# MARINEFORD.net
KiCad netlist of a schematic drawn in EAGLE
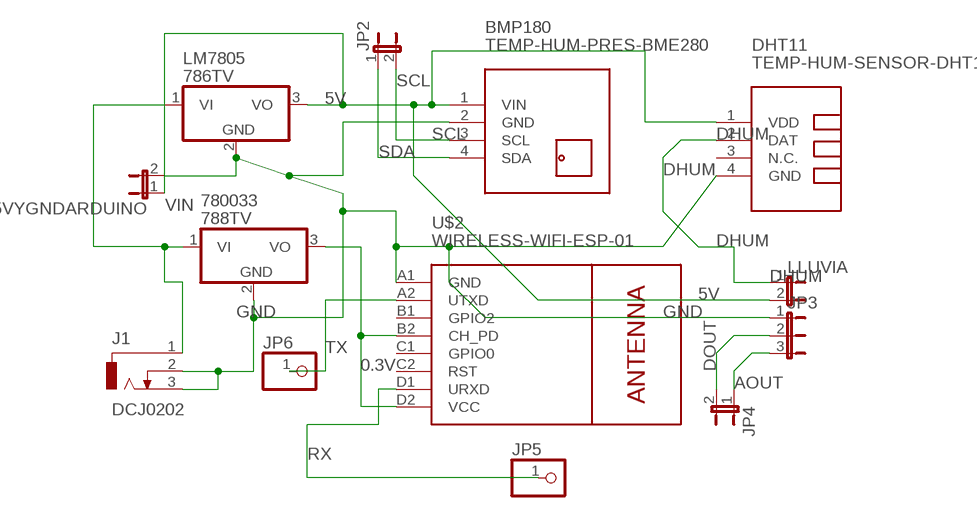
[diagram p0: schematic, sheet 1]

(export (version "E")
  (design (tool "Eeschema 10.0.6"))
  (components
    (comp (ref "5VYGNDARDUINO")
      (value "JP1E")
      (footprint "eagle-import:JP1")
      (libsource (lib "eagle-import") (part "JP1E"))
    )
    (comp (ref "780033")
      (value "788TV")
      (footprint "eagle-import:TO220V")
      (libsource (lib "eagle-import") (part "78TV8"))
    )
    (comp (ref "BMP180")
      (value "TEMP-HUM-PRES-BME280")
      (footprint "eagle-import:TEMP-HUM-PRES-BME280")
      (libsource (lib "eagle-import") (part "TEMP-HUM-PRES-BME280"))
    )
    (comp (ref "DHT11")
      (value "TEMP-HUM-SENSOR-DHT11")
      (footprint "eagle-import:TEMP-HUM-SENSOR-DHT11")
      (libsource (lib "eagle-import") (part "TEMP-HUM-SENSOR-DHT11"))
    )
    (comp (ref "J1")
      (value "DCJ0202")
      (footprint "eagle-import:DCJ0202")
      (libsource (lib "eagle-import") (part "DCJ0202"))
    )
    (comp (ref "JP2")
      (value "JP1E")
      (footprint "eagle-import:JP1")
      (libsource (lib "eagle-import") (part "JP1E"))
    )
    (comp (ref "JP3")
      (value "JP2E")
      (footprint "eagle-import:JP2")
      (libsource (lib "eagle-import") (part "JP2E"))
    )
    (comp (ref "JP4")
      (value "JP1E")
      (footprint "eagle-import:JP1")
      (libsource (lib "eagle-import") (part "JP1E"))
    )
    (comp (ref "JP5")
      (value "PINHD-1X1")
      (footprint "eagle-import:1X01")
      (libsource (lib "eagle-import") (part "PINHD-1X1"))
    )
    (comp (ref "JP6")
      (value "PINHD-1X1")
      (footprint "eagle-import:1X01")
      (libsource (lib "eagle-import") (part "PINHD-1X1"))
    )
    (comp (ref "LLUVIA")
      (value "JP1E")
      (footprint "eagle-import:JP1")
      (libsource (lib "eagle-import") (part "JP1E"))
    )
    (comp (ref "LM7805")
      (value "786TV")
      (footprint "eagle-import:TO220V")
      (libsource (lib "eagle-import") (part "78TV6"))
    )
    (comp (ref "U$2")
      (value "WIRELESS-WIFI-ESP-01")
      (footprint "eagle-import:WIRELESS-WIFI-ESP-01")
      (libsource (lib "eagle-import") (part "WIRELESS-WIFI-ESP-01"))
    )
  )
  (nets
    (net (code "1") (name "/0.3V") (class "Default")
      (node (ref "780033") (pin "3") (pinfunction "VO_3") (pintype "passive"))
      (node (ref "U$2") (pin "B2") (pinfunction "CH_PD_B2") (pintype "bidirectional"))
      (node (ref "U$2") (pin "D2") (pinfunction "VCC_D2") (pintype "power_in"))
    )
    (net (code "2") (name "/5V") (class "Default")
      (node (ref "5VYGNDARDUINO") (pin "1") (pinfunction "1_1") (pintype "passive"))
      (node (ref "BMP180") (pin "1") (pinfunction "VIN_1") (pintype "power_in"))
      (node (ref "DHT11") (pin "1") (pinfunction "VDD_1") (pintype "power_in"))
      (node (ref "LLUVIA") (pin "2") (pinfunction "2_2") (pintype "passive"))
      (node (ref "LM7805") (pin "3") (pinfunction "VO_3") (pintype "passive"))
    )
    (net (code "3") (name "/AOUT") (class "Default")
      (node (ref "JP3") (pin "3") (pinfunction "3_3") (pintype "passive"))
      (node (ref "JP4") (pin "1") (pinfunction "1_1") (pintype "passive"))
    )
    (net (code "4") (name "/DHUM") (class "Default")
      (node (ref "DHT11") (pin "2") (pinfunction "DAT_2") (pintype "bidirectional"))
      (node (ref "LLUVIA") (pin "1") (pinfunction "1_1") (pintype "passive"))
    )
    (net (code "5") (name "/DOUT") (class "Default")
      (node (ref "JP3") (pin "2") (pinfunction "2_2") (pintype "passive"))
      (node (ref "JP4") (pin "2") (pinfunction "2_2") (pintype "passive"))
    )
    (net (code "6") (name "/GND") (class "Default")
      (node (ref "5VYGNDARDUINO") (pin "2") (pinfunction "2_2") (pintype "passive"))
      (node (ref "780033") (pin "2") (pinfunction "GND_2") (pintype "passive"))
      (node (ref "BMP180") (pin "2") (pinfunction "GND_2") (pintype "power_in"))
      (node (ref "DHT11") (pin "4") (pinfunction "GND_4") (pintype "power_in"))
      (node (ref "J1") (pin "2") (pinfunction "2_2") (pintype "passive"))
      (node (ref "J1") (pin "3") (pinfunction "3_3") (pintype "passive"))
      (node (ref "JP3") (pin "1") (pinfunction "1_1") (pintype "passive"))
      (node (ref "LM7805") (pin "2") (pinfunction "GND_2") (pintype "passive"))
      (node (ref "U$2") (pin "A1") (pinfunction "GND_A1") (pintype "power_in"))
    )
    (net (code "7") (name "/RX") (class "Default")
      (node (ref "JP5") (pin "1") (pinfunction "1_1") (pintype "passive"))
      (node (ref "U$2") (pin "D1") (pinfunction "URXD_D1") (pintype "bidirectional"))
    )
    (net (code "8") (name "/SCL") (class "Default")
      (node (ref "BMP180") (pin "3") (pinfunction "SCL_3") (pintype "bidirectional"))
      (node (ref "JP2") (pin "2") (pinfunction "2_2") (pintype "passive"))
    )
    (net (code "9") (name "/SDA") (class "Default")
      (node (ref "BMP180") (pin "4") (pinfunction "SDA_4") (pintype "bidirectional"))
      (node (ref "JP2") (pin "1") (pinfunction "1_1") (pintype "passive"))
    )
    (net (code "10") (name "/TX") (class "Default")
      (node (ref "JP6") (pin "1") (pinfunction "1_1") (pintype "passive"))
      (node (ref "U$2") (pin "A2") (pinfunction "UTXD_A2") (pintype "bidirectional"))
    )
    (net (code "11") (name "/VIN") (class "Default")
      (node (ref "780033") (pin "1") (pinfunction "VI_1") (pintype "input"))
      (node (ref "J1") (pin "1") (pinfunction "1_1") (pintype "passive"))
      (node (ref "LM7805") (pin "1") (pinfunction "VI_1") (pintype "input"))
    )
    (net (code "12") (name "unconnected-(DHT11-N.C.-Pad3)") (class "Default")
      (node (ref "DHT11") (pin "3") (pinfunction "N.C._3") (pintype "passive"))
    )
    (net (code "13") (name "unconnected-(U$2-GPIO0-PadC1)") (class "Default")
      (node (ref "U$2") (pin "C1") (pinfunction "GPIO0_C1") (pintype "bidirectional"))
    )
    (net (code "14") (name "unconnected-(U$2-GPIO2-PadB1)") (class "Default")
      (node (ref "U$2") (pin "B1") (pinfunction "GPIO2_B1") (pintype "bidirectional"))
    )
    (net (code "15") (name "unconnected-(U$2-RST-PadC2)") (class "Default")
      (node (ref "U$2") (pin "C2") (pinfunction "RST_C2") (pintype "bidirectional"))
    )
  )
)
